# Prescaler_HMC862A.net
KiCad netlist of a schematic drawn in Altium Designer
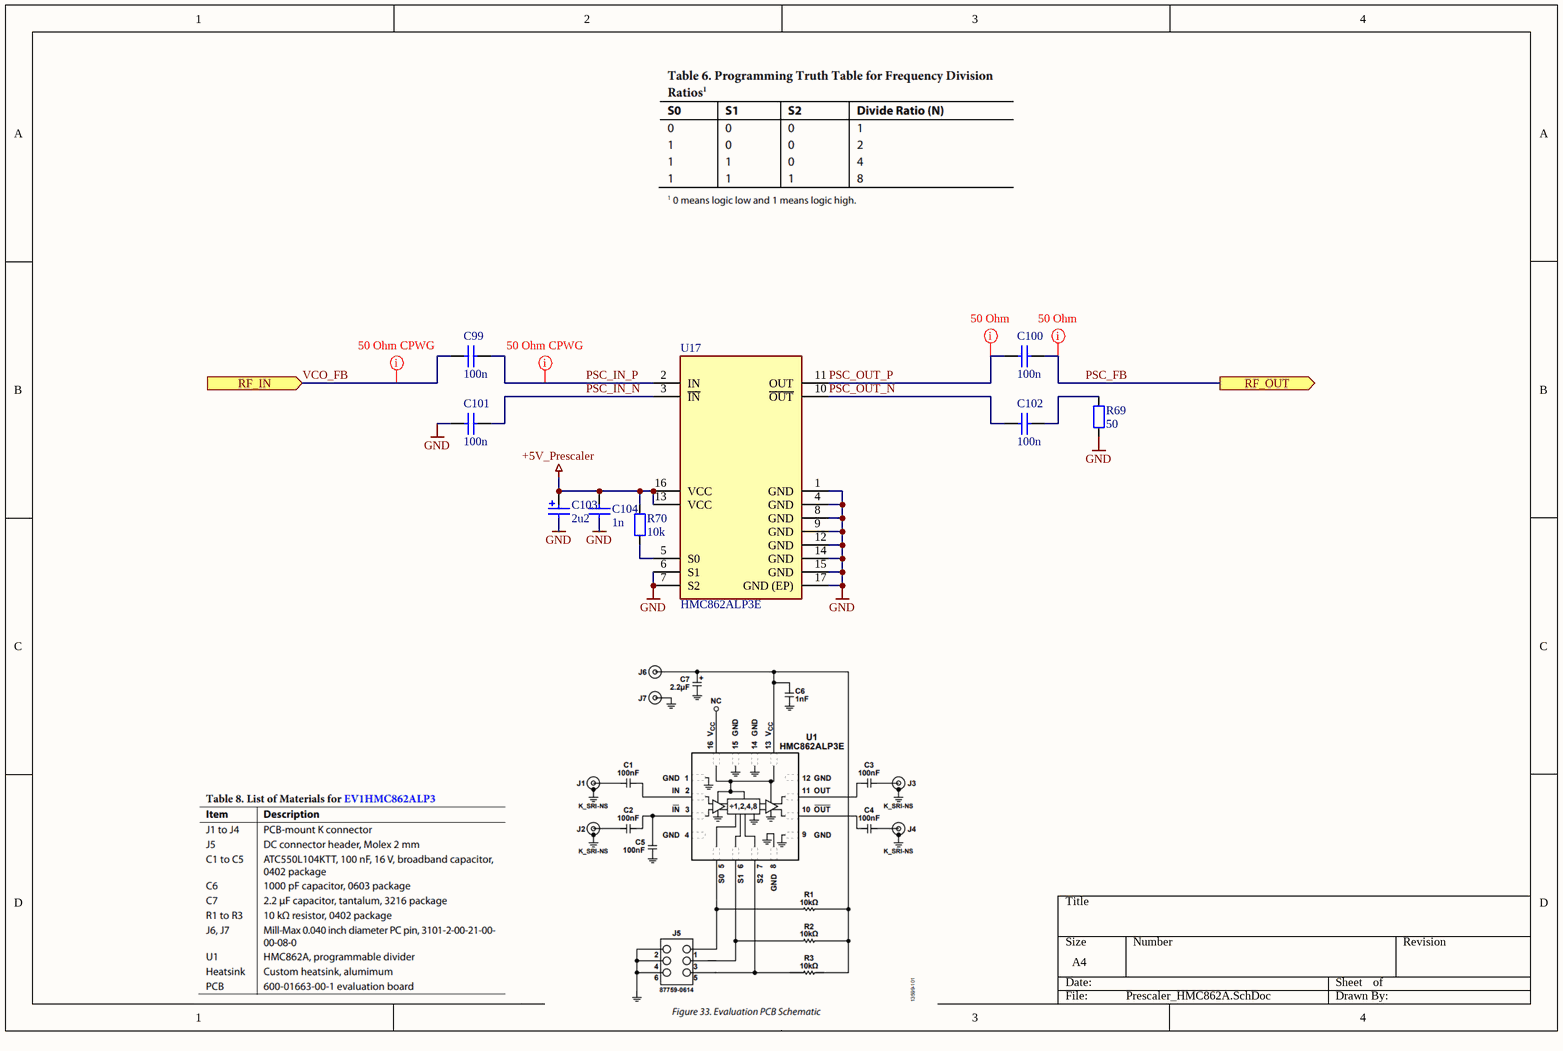
[diagram p0: Prescaler_HMC862A.SchDoc]

(export (version "E")
  (design (tool "Eeschema 10.0.6"))
  (components
    (comp (ref "C99")
      (value "100n")
      (footprint "C_0402_1005Metric_IPC_N")
      (description "Generic MLCC with 0402 Footprint")
      (libsource (lib "database_library") (part "Capacitor_unpol"))
    )
    (comp (ref "C100")
      (value "100n")
      (footprint "C_0402_1005Metric_IPC_N")
      (description "Generic MLCC with 0402 Footprint")
      (libsource (lib "database_library") (part "Capacitor_unpol"))
    )
    (comp (ref "C101")
      (value "100n")
      (footprint "C_0402_1005Metric_IPC_N")
      (description "Generic MLCC with 0402 Footprint")
      (libsource (lib "database_library") (part "Capacitor_unpol"))
    )
    (comp (ref "C102")
      (value "100n")
      (footprint "C_0402_1005Metric_IPC_N")
      (description "Generic MLCC with 0402 Footprint")
      (libsource (lib "database_library") (part "Capacitor_unpol"))
    )
    (comp (ref "C103")
      (value "2u2")
      (footprint "C_1206_3216Metric_Pol_IPC_N")
      (description "Generic MLCC with 1206 Footprint")
      (libsource (lib "database_library") (part "Capacitor_pol"))
    )
    (comp (ref "C104")
      (value "1n")
      (footprint "C_0603_1608Metric_IPC_N")
      (description "Generic MLCC with 0603 Footprint")
      (libsource (lib "database_library") (part "Capacitor_unpol"))
    )
    (comp (ref "R69")
      (value "50")
      (footprint "R_0402_1005Metric_IPC_N")
      (description "Generic Chip Resistor with 0402 Footprint")
      (libsource (lib "database_library") (part "Resistor"))
    )
    (comp (ref "R70")
      (value "10k")
      (footprint "R_0402_1005Metric_IPC_N")
      (description "Generic Chip Resistor with 0402 Footprint")
      (libsource (lib "database_library") (part "Resistor"))
    )
    (comp (ref "U17")
      (value "HMC862ALP3E")
      (footprint "LFCSP-16-1EP_3x3mm_P0.5mm_EP1.7x1.7mm_IPC_N")
      (description "Prescaler 5V Divide By 1/2/4/8 24000MHz 16-Pin LFCSP EP Cut Tape")
      (fields
        (field (name "MOUSER PART NUMBER") "584-HMC862ALP3E")
        (field (name "MANUFACTURER") "Analog Devices")
      )
      (libsource (lib "database_library") (part "HMC862ALP3E"))
    )
  )
  (nets
    (net (code "1") (name "+5V_Prescaler") (class "Default")
      (node (ref "C103") (pin "1") (pinfunction "1_1") (pintype "passive"))
      (node (ref "C104") (pin "2") (pinfunction "2_2") (pintype "passive"))
      (node (ref "R70") (pin "1") (pinfunction "1_1") (pintype "passive"))
      (node (ref "U17") (pin "13") (pinfunction "VCC_13") (pintype "passive"))
      (node (ref "U17") (pin "16") (pinfunction "VCC_16") (pintype "passive"))
    )
    (net (code "2") (name "/PSC_FB") (class "Default")
      (node (ref "C100") (pin "2") (pinfunction "2_2") (pintype "passive"))
    )
    (net (code "3") (name "/PSC_IN_N") (class "Default")
      (node (ref "C101") (pin "1") (pinfunction "1_1") (pintype "passive"))
      (node (ref "U17") (pin "3") (pinfunction "~{IN}_3") (pintype "passive"))
    )
    (net (code "4") (name "/PSC_IN_P") (class "Default")
      (node (ref "C99") (pin "1") (pinfunction "1_1") (pintype "passive"))
      (node (ref "U17") (pin "2") (pinfunction "IN_2") (pintype "passive"))
    )
    (net (code "5") (name "/PSC_OUT_N") (class "Default")
      (node (ref "C102") (pin "1") (pinfunction "1_1") (pintype "passive"))
      (node (ref "U17") (pin "10") (pinfunction "~{OUT}_10") (pintype "passive"))
    )
    (net (code "6") (name "/PSC_OUT_P") (class "Default")
      (node (ref "C100") (pin "1") (pinfunction "1_1") (pintype "passive"))
      (node (ref "U17") (pin "11") (pinfunction "OUT_11") (pintype "passive"))
    )
    (net (code "7") (name "/VCO_FB") (class "Default")
      (node (ref "C99") (pin "2") (pinfunction "2_2") (pintype "passive"))
    )
    (net (code "8") (name "GND") (class "Default")
      (node (ref "C101") (pin "2") (pinfunction "2_2") (pintype "passive"))
      (node (ref "C103") (pin "2") (pinfunction "2_2") (pintype "passive"))
      (node (ref "C104") (pin "1") (pinfunction "1_1") (pintype "passive"))
      (node (ref "R69") (pin "1") (pinfunction "1_1") (pintype "passive"))
      (node (ref "U17") (pin "1") (pinfunction "GND_1") (pintype "passive"))
      (node (ref "U17") (pin "12") (pinfunction "GND_12") (pintype "passive"))
      (node (ref "U17") (pin "14") (pinfunction "GND_14") (pintype "passive"))
      (node (ref "U17") (pin "15") (pinfunction "GND_15") (pintype "passive"))
      (node (ref "U17") (pin "17") (pinfunction "GND_(EP)_17") (pintype "passive"))
      (node (ref "U17") (pin "4") (pinfunction "GND_4") (pintype "passive"))
      (node (ref "U17") (pin "6") (pinfunction "S1_6") (pintype "passive"))
      (node (ref "U17") (pin "7") (pinfunction "S2_7") (pintype "passive"))
      (node (ref "U17") (pin "8") (pinfunction "GND_8") (pintype "passive"))
      (node (ref "U17") (pin "9") (pinfunction "GND_9") (pintype "passive"))
    )
    (net (code "9") (name "Net-(C102-Pad2)") (class "Default")
      (node (ref "C102") (pin "2") (pinfunction "2_2") (pintype "passive"))
      (node (ref "R69") (pin "2") (pinfunction "2_2") (pintype "passive"))
    )
    (net (code "10") (name "Net-(U17-S0)") (class "Default")
      (node (ref "R70") (pin "2") (pinfunction "2_2") (pintype "passive"))
      (node (ref "U17") (pin "5") (pinfunction "S0_5") (pintype "passive"))
    )
  )
)
